# lzond1.net
KiCad netlist of a schematic drawn in EAGLE
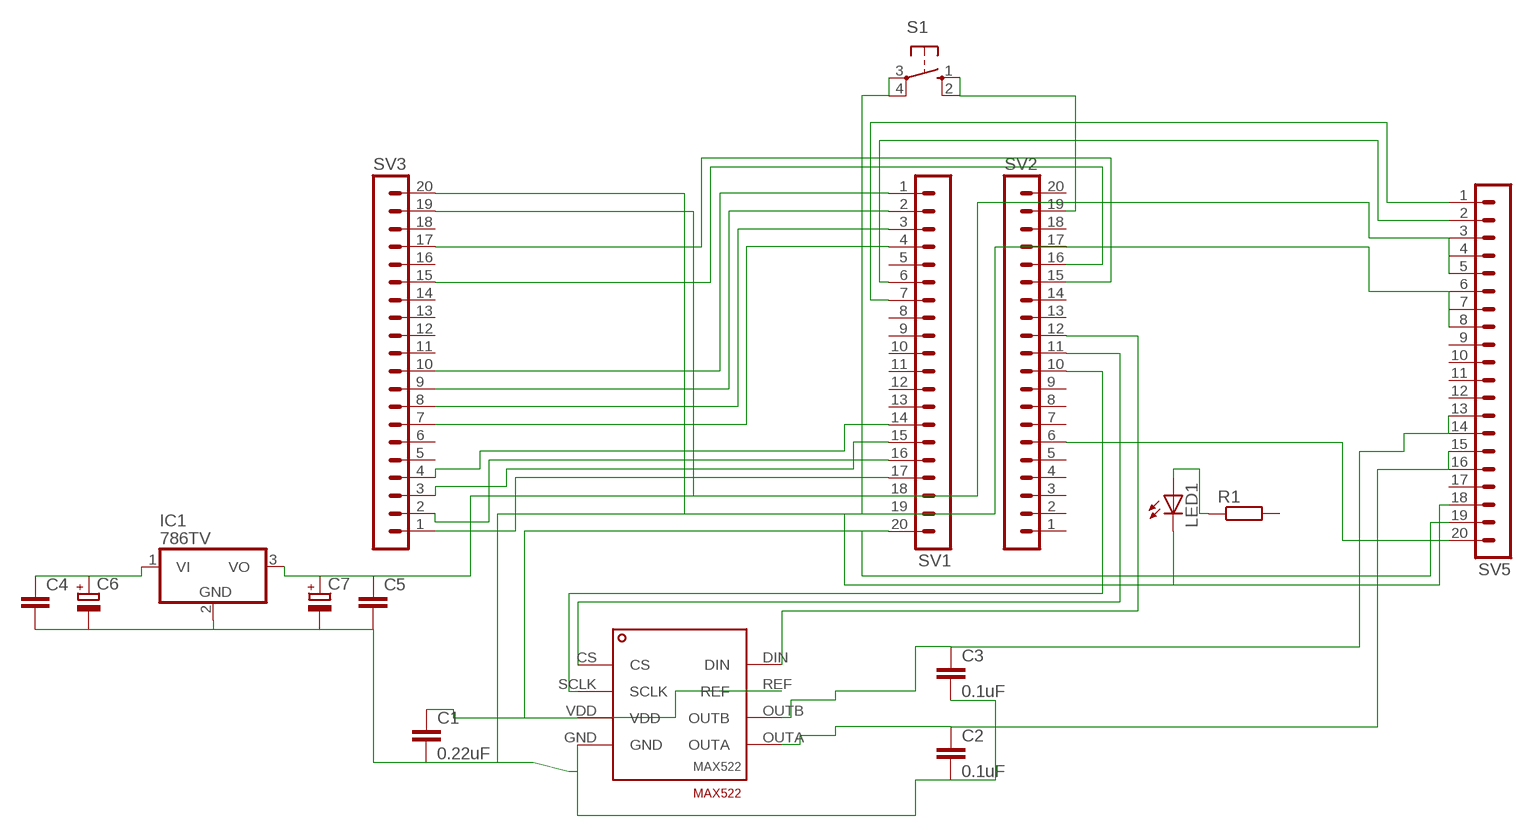
[diagram p0: schematic, sheet 1]

(export (version "E")
  (design (tool "Eeschema 10.0.6"))
  (components
    (comp (ref "C1")
      (value "0.22uF")
      (footprint "eagle-import:C0805")
      (libsource (lib "eagle-import") (part "C-EUC0805"))
    )
    (comp (ref "C2")
      (value "0.1uF")
      (footprint "eagle-import:C0805")
      (libsource (lib "eagle-import") (part "C-EUC0805"))
    )
    (comp (ref "C3")
      (value "0.1uF")
      (footprint "eagle-import:C0805")
      (libsource (lib "eagle-import") (part "C-EUC0805"))
    )
    (comp (ref "C4")
      (value "C-EUC1210")
      (footprint "eagle-import:C1210")
      (libsource (lib "eagle-import") (part "resistor_C-EUC1210"))
    )
    (comp (ref "C5")
      (value "C-EUC1210")
      (footprint "eagle-import:C1210")
      (libsource (lib "eagle-import") (part "resistor_C-EUC1210"))
    )
    (comp (ref "C6")
      (value "CPOL-EUE5-8.5")
      (footprint "eagle-import:E5-8,5")
      (libsource (lib "eagle-import") (part "CPOL-EUE5-8.5"))
    )
    (comp (ref "C7")
      (value "CPOL-EUE5-8.5")
      (footprint "eagle-import:E5-8,5")
      (libsource (lib "eagle-import") (part "CPOL-EUE5-8.5"))
    )
    (comp (ref "IC1")
      (value "786TV")
      (footprint "eagle-import:TO220V")
      (libsource (lib "eagle-import") (part "78TV6"))
    )
    (comp (ref "LED1")
      (value "LED3MM")
      (footprint "eagle-import:LED3MM")
      (libsource (lib "eagle-import") (part "LED3MM"))
    )
    (comp (ref "R1")
      (value "R-EU_R0805")
      (footprint "eagle-import:R0805")
      (libsource (lib "eagle-import") (part "R-EU_R0805"))
    )
    (comp (ref "S1")
      (value "10-XX")
      (footprint "eagle-import:B3F-10XX")
      (fields (field (name "MPN") "B3F-1000"))
      (libsource (lib "eagle-import") (part "10-XX"))
    )
    (comp (ref "SV1")
      (value "MA20-1")
      (footprint "eagle-import:MA20-1")
      (libsource (lib "eagle-import") (part "MA20-1"))
    )
    (comp (ref "SV2")
      (value "MA20-1")
      (footprint "eagle-import:MA20-1")
      (libsource (lib "eagle-import") (part "MA20-1"))
    )
    (comp (ref "SV3")
      (value "MA20-1")
      (footprint "eagle-import:MA20-1")
      (libsource (lib "eagle-import") (part "MA20-1"))
    )
    (comp (ref "SV5")
      (value "MA20-1")
      (footprint "eagle-import:MA20-1")
      (libsource (lib "eagle-import") (part "MA20-1"))
    )
    (comp (ref "U$2")
      (value "MAX522")
      (footprint "eagle-import:MAX522")
      (libsource (lib "eagle-import") (part "MAX522"))
    )
  )
  (nets
    (net (code "1") (name "Net-(C1-Pad1)") (class "Default")
      (node (ref "C1") (pin "1") (pinfunction "1_1") (pintype "passive"))
      (node (ref "SV1") (pin "20") (pinfunction "20_20") (pintype "passive"))
      (node (ref "SV5") (pin "19") (pinfunction "19_19") (pintype "passive"))
      (node (ref "U$2") (pin "REF") (pinfunction "REF_REF") (pintype "power_in"))
      (node (ref "U$2") (pin "VDD") (pinfunction "VDD_VDD") (pintype "power_in"))
    )
    (net (code "2") (name "Net-(C2-Pad1)") (class "Default")
      (node (ref "C2") (pin "1") (pinfunction "1_1") (pintype "passive"))
      (node (ref "SV5") (pin "15") (pinfunction "15_15") (pintype "passive"))
      (node (ref "SV5") (pin "16") (pinfunction "16_16") (pintype "passive"))
      (node (ref "U$2") (pin "OUTA") (pinfunction "OUTA_OUTA") (pintype "output"))
    )
    (net (code "3") (name "Net-(C3-Pad1)") (class "Default")
      (node (ref "C3") (pin "1") (pinfunction "1_1") (pintype "passive"))
      (node (ref "SV5") (pin "13") (pinfunction "13_13") (pintype "passive"))
      (node (ref "SV5") (pin "14") (pinfunction "14_14") (pintype "passive"))
      (node (ref "U$2") (pin "OUTB") (pinfunction "OUTB_OUTB") (pintype "output"))
    )
    (net (code "4") (name "Net-(IC1-GND)") (class "Default")
      (node (ref "C1") (pin "2") (pinfunction "2_2") (pintype "passive"))
      (node (ref "C2") (pin "2") (pinfunction "2_2") (pintype "passive"))
      (node (ref "C3") (pin "2") (pinfunction "2_2") (pintype "passive"))
      (node (ref "C4") (pin "2") (pinfunction "2_2") (pintype "passive"))
      (node (ref "C5") (pin "2") (pinfunction "2_2") (pintype "passive"))
      (node (ref "C6") (pin "-") (pinfunction "-_-") (pintype "passive"))
      (node (ref "C7") (pin "-") (pinfunction "-_-") (pintype "passive"))
      (node (ref "IC1") (pin "2") (pinfunction "GND_2") (pintype "passive"))
      (node (ref "LED1") (pin "K") (pinfunction "C_K") (pintype "passive"))
      (node (ref "S1") (pin "3") (pinfunction "P_3") (pintype "passive"))
      (node (ref "S1") (pin "4") (pinfunction "P1_4") (pintype "passive"))
      (node (ref "SV1") (pin "19") (pinfunction "19_19") (pintype "passive"))
      (node (ref "SV3") (pin "20") (pinfunction "20_20") (pintype "passive"))
      (node (ref "SV5") (pin "18") (pinfunction "18_18") (pintype "passive"))
      (node (ref "SV5") (pin "6") (pinfunction "6_6") (pintype "passive"))
      (node (ref "SV5") (pin "7") (pinfunction "7_7") (pintype "passive"))
      (node (ref "SV5") (pin "8") (pinfunction "8_8") (pintype "passive"))
      (node (ref "U$2") (pin "GND") (pinfunction "GND_GND") (pintype "power_in"))
    )
    (net (code "5") (name "Net-(IC1-VI)") (class "Default")
      (node (ref "C4") (pin "1") (pinfunction "1_1") (pintype "passive"))
      (node (ref "C6") (pin "+") (pinfunction "+_+") (pintype "passive"))
      (node (ref "IC1") (pin "1") (pinfunction "VI_1") (pintype "input"))
    )
    (net (code "6") (name "Net-(IC1-VO)") (class "Default")
      (node (ref "C5") (pin "1") (pinfunction "1_1") (pintype "passive"))
      (node (ref "C7") (pin "+") (pinfunction "+_+") (pintype "passive"))
      (node (ref "IC1") (pin "3") (pinfunction "VO_3") (pintype "passive"))
      (node (ref "SV1") (pin "18") (pinfunction "18_18") (pintype "passive"))
      (node (ref "SV3") (pin "19") (pinfunction "19_19") (pintype "passive"))
      (node (ref "SV5") (pin "3") (pinfunction "3_3") (pintype "passive"))
      (node (ref "SV5") (pin "4") (pinfunction "4_4") (pintype "passive"))
      (node (ref "SV5") (pin "5") (pinfunction "5_5") (pintype "passive"))
    )
    (net (code "7") (name "Net-(LED1-PadA)") (class "Default")
      (node (ref "LED1") (pin "A") (pinfunction "A_A") (pintype "passive"))
      (node (ref "R1") (pin "1") (pinfunction "1_1") (pintype "passive"))
    )
    (net (code "8") (name "Net-(S1-S)") (class "Default")
      (node (ref "S1") (pin "1") (pinfunction "S_1") (pintype "passive"))
      (node (ref "S1") (pin "2") (pinfunction "S1_2") (pintype "passive"))
      (node (ref "SV2") (pin "19") (pinfunction "19_19") (pintype "passive"))
    )
    (net (code "9") (name "Net-(SV1-Pad1)") (class "Default")
      (node (ref "SV1") (pin "1") (pinfunction "1_1") (pintype "passive"))
      (node (ref "SV3") (pin "10") (pinfunction "10_10") (pintype "passive"))
    )
    (net (code "10") (name "Net-(SV1-Pad2)") (class "Default")
      (node (ref "SV1") (pin "2") (pinfunction "2_2") (pintype "passive"))
      (node (ref "SV3") (pin "9") (pinfunction "9_9") (pintype "passive"))
    )
    (net (code "11") (name "Net-(SV1-Pad3)") (class "Default")
      (node (ref "SV1") (pin "3") (pinfunction "3_3") (pintype "passive"))
      (node (ref "SV3") (pin "8") (pinfunction "8_8") (pintype "passive"))
    )
    (net (code "12") (name "Net-(SV1-Pad4)") (class "Default")
      (node (ref "SV1") (pin "4") (pinfunction "4_4") (pintype "passive"))
      (node (ref "SV3") (pin "7") (pinfunction "7_7") (pintype "passive"))
    )
    (net (code "13") (name "Net-(SV1-Pad6)") (class "Default")
      (node (ref "SV1") (pin "6") (pinfunction "6_6") (pintype "passive"))
      (node (ref "SV5") (pin "2") (pinfunction "2_2") (pintype "passive"))
    )
    (net (code "14") (name "Net-(SV1-Pad7)") (class "Default")
      (node (ref "SV1") (pin "7") (pinfunction "7_7") (pintype "passive"))
      (node (ref "SV5") (pin "1") (pinfunction "1_1") (pintype "passive"))
    )
    (net (code "15") (name "Net-(SV1-Pad14)") (class "Default")
      (node (ref "SV1") (pin "14") (pinfunction "14_14") (pintype "passive"))
      (node (ref "SV3") (pin "4") (pinfunction "4_4") (pintype "passive"))
    )
    (net (code "16") (name "Net-(SV1-Pad15)") (class "Default")
      (node (ref "SV1") (pin "15") (pinfunction "15_15") (pintype "passive"))
      (node (ref "SV3") (pin "3") (pinfunction "3_3") (pintype "passive"))
    )
    (net (code "17") (name "Net-(SV1-Pad16)") (class "Default")
      (node (ref "SV1") (pin "16") (pinfunction "16_16") (pintype "passive"))
      (node (ref "SV3") (pin "2") (pinfunction "2_2") (pintype "passive"))
    )
    (net (code "18") (name "Net-(SV1-Pad17)") (class "Default")
      (node (ref "SV1") (pin "17") (pinfunction "17_17") (pintype "passive"))
      (node (ref "SV3") (pin "1") (pinfunction "1_1") (pintype "passive"))
    )
    (net (code "19") (name "Net-(SV2-Pad6)") (class "Default")
      (node (ref "SV2") (pin "6") (pinfunction "6_6") (pintype "passive"))
      (node (ref "SV5") (pin "20") (pinfunction "20_20") (pintype "passive"))
    )
    (net (code "20") (name "Net-(SV2-Pad10)") (class "Default")
      (node (ref "SV2") (pin "10") (pinfunction "10_10") (pintype "passive"))
      (node (ref "U$2") (pin "SCLK") (pinfunction "SCLK_SCLK") (pintype "input"))
    )
    (net (code "21") (name "Net-(SV2-Pad11)") (class "Default")
      (node (ref "SV2") (pin "11") (pinfunction "11_11") (pintype "passive"))
      (node (ref "U$2") (pin "CS") (pinfunction "CS_CS") (pintype "input"))
    )
    (net (code "22") (name "Net-(SV2-Pad12)") (class "Default")
      (node (ref "SV2") (pin "12") (pinfunction "12_12") (pintype "passive"))
      (node (ref "U$2") (pin "DIN") (pinfunction "DIN_DIN") (pintype "input"))
    )
    (net (code "23") (name "Net-(SV2-Pad15)") (class "Default")
      (node (ref "SV2") (pin "15") (pinfunction "15_15") (pintype "passive"))
      (node (ref "SV3") (pin "17") (pinfunction "17_17") (pintype "passive"))
    )
    (net (code "24") (name "Net-(SV2-Pad16)") (class "Default")
      (node (ref "SV2") (pin "16") (pinfunction "16_16") (pintype "passive"))
      (node (ref "SV3") (pin "15") (pinfunction "15_15") (pintype "passive"))
    )
    (net (code "25") (name "unconnected-(R1-Pad2)") (class "Default")
      (node (ref "R1") (pin "2") (pinfunction "2_2") (pintype "passive"))
    )
    (net (code "26") (name "unconnected-(SV1-Pad5)") (class "Default")
      (node (ref "SV1") (pin "5") (pinfunction "5_5") (pintype "passive"))
    )
    (net (code "27") (name "unconnected-(SV1-Pad8)") (class "Default")
      (node (ref "SV1") (pin "8") (pinfunction "8_8") (pintype "passive"))
    )
    (net (code "28") (name "unconnected-(SV1-Pad9)") (class "Default")
      (node (ref "SV1") (pin "9") (pinfunction "9_9") (pintype "passive"))
    )
    (net (code "29") (name "unconnected-(SV1-Pad10)") (class "Default")
      (node (ref "SV1") (pin "10") (pinfunction "10_10") (pintype "passive"))
    )
    (net (code "30") (name "unconnected-(SV1-Pad11)") (class "Default")
      (node (ref "SV1") (pin "11") (pinfunction "11_11") (pintype "passive"))
    )
    (net (code "31") (name "unconnected-(SV1-Pad12)") (class "Default")
      (node (ref "SV1") (pin "12") (pinfunction "12_12") (pintype "passive"))
    )
    (net (code "32") (name "unconnected-(SV1-Pad13)") (class "Default")
      (node (ref "SV1") (pin "13") (pinfunction "13_13") (pintype "passive"))
    )
    (net (code "33") (name "unconnected-(SV2-Pad1)") (class "Default")
      (node (ref "SV2") (pin "1") (pinfunction "1_1") (pintype "passive"))
    )
    (net (code "34") (name "unconnected-(SV2-Pad2)") (class "Default")
      (node (ref "SV2") (pin "2") (pinfunction "2_2") (pintype "passive"))
    )
    (net (code "35") (name "unconnected-(SV2-Pad3)") (class "Default")
      (node (ref "SV2") (pin "3") (pinfunction "3_3") (pintype "passive"))
    )
    (net (code "36") (name "unconnected-(SV2-Pad4)") (class "Default")
      (node (ref "SV2") (pin "4") (pinfunction "4_4") (pintype "passive"))
    )
    (net (code "37") (name "unconnected-(SV2-Pad5)") (class "Default")
      (node (ref "SV2") (pin "5") (pinfunction "5_5") (pintype "passive"))
    )
    (net (code "38") (name "unconnected-(SV2-Pad7)") (class "Default")
      (node (ref "SV2") (pin "7") (pinfunction "7_7") (pintype "passive"))
    )
    (net (code "39") (name "unconnected-(SV2-Pad8)") (class "Default")
      (node (ref "SV2") (pin "8") (pinfunction "8_8") (pintype "passive"))
    )
    (net (code "40") (name "unconnected-(SV2-Pad9)") (class "Default")
      (node (ref "SV2") (pin "9") (pinfunction "9_9") (pintype "passive"))
    )
    (net (code "41") (name "unconnected-(SV2-Pad13)") (class "Default")
      (node (ref "SV2") (pin "13") (pinfunction "13_13") (pintype "passive"))
    )
    (net (code "42") (name "unconnected-(SV2-Pad14)") (class "Default")
      (node (ref "SV2") (pin "14") (pinfunction "14_14") (pintype "passive"))
    )
    (net (code "43") (name "unconnected-(SV2-Pad17)") (class "Default")
      (node (ref "SV2") (pin "17") (pinfunction "17_17") (pintype "passive"))
    )
    (net (code "44") (name "unconnected-(SV2-Pad18)") (class "Default")
      (node (ref "SV2") (pin "18") (pinfunction "18_18") (pintype "passive"))
    )
    (net (code "45") (name "unconnected-(SV2-Pad20)") (class "Default")
      (node (ref "SV2") (pin "20") (pinfunction "20_20") (pintype "passive"))
    )
    (net (code "46") (name "unconnected-(SV3-Pad5)") (class "Default")
      (node (ref "SV3") (pin "5") (pinfunction "5_5") (pintype "passive"))
    )
    (net (code "47") (name "unconnected-(SV3-Pad6)") (class "Default")
      (node (ref "SV3") (pin "6") (pinfunction "6_6") (pintype "passive"))
    )
    (net (code "48") (name "unconnected-(SV3-Pad11)") (class "Default")
      (node (ref "SV3") (pin "11") (pinfunction "11_11") (pintype "passive"))
    )
    (net (code "49") (name "unconnected-(SV3-Pad12)") (class "Default")
      (node (ref "SV3") (pin "12") (pinfunction "12_12") (pintype "passive"))
    )
    (net (code "50") (name "unconnected-(SV3-Pad13)") (class "Default")
      (node (ref "SV3") (pin "13") (pinfunction "13_13") (pintype "passive"))
    )
    (net (code "51") (name "unconnected-(SV3-Pad14)") (class "Default")
      (node (ref "SV3") (pin "14") (pinfunction "14_14") (pintype "passive"))
    )
    (net (code "52") (name "unconnected-(SV3-Pad16)") (class "Default")
      (node (ref "SV3") (pin "16") (pinfunction "16_16") (pintype "passive"))
    )
    (net (code "53") (name "unconnected-(SV3-Pad18)") (class "Default")
      (node (ref "SV3") (pin "18") (pinfunction "18_18") (pintype "passive"))
    )
    (net (code "54") (name "unconnected-(SV5-Pad9)") (class "Default")
      (node (ref "SV5") (pin "9") (pinfunction "9_9") (pintype "passive"))
    )
    (net (code "55") (name "unconnected-(SV5-Pad10)") (class "Default")
      (node (ref "SV5") (pin "10") (pinfunction "10_10") (pintype "passive"))
    )
    (net (code "56") (name "unconnected-(SV5-Pad11)") (class "Default")
      (node (ref "SV5") (pin "11") (pinfunction "11_11") (pintype "passive"))
    )
    (net (code "57") (name "unconnected-(SV5-Pad12)") (class "Default")
      (node (ref "SV5") (pin "12") (pinfunction "12_12") (pintype "passive"))
    )
    (net (code "58") (name "unconnected-(SV5-Pad17)") (class "Default")
      (node (ref "SV5") (pin "17") (pinfunction "17_17") (pintype "passive"))
    )
  )
)
